# cs301_Team_15.net
KiCad netlist of a schematic drawn in Altium Designer
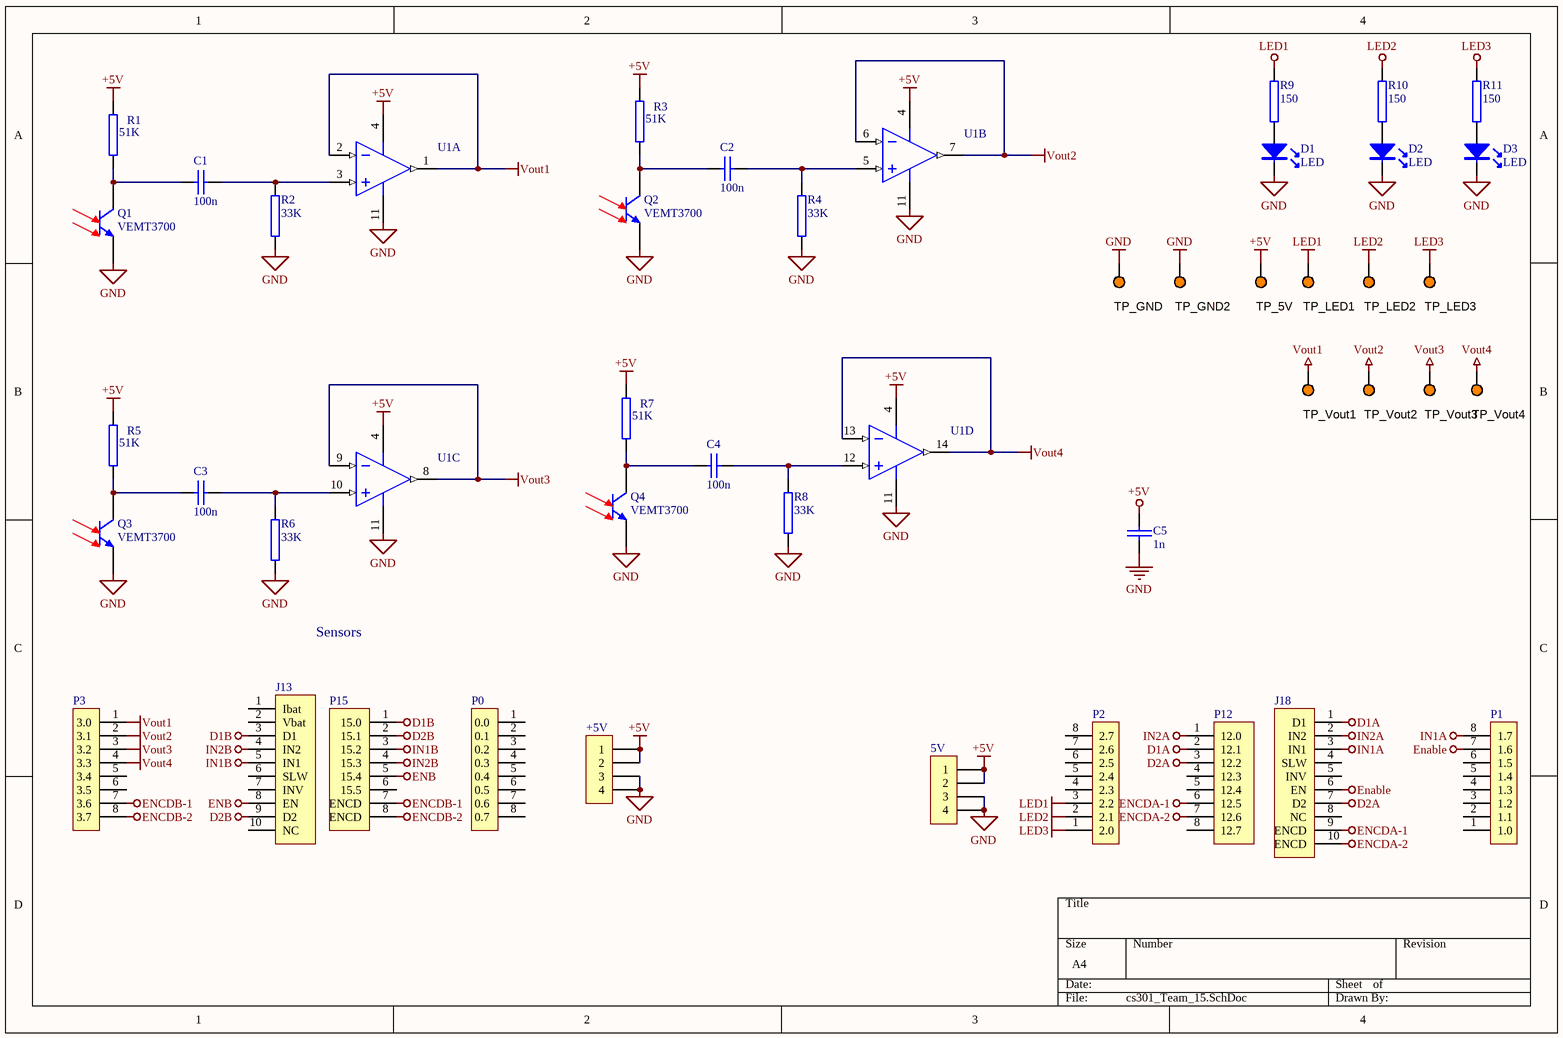
[diagram p0: cs301_Team_15.SchDoc]

(export (version "E")
  (design (tool "Eeschema 10.0.6"))
  (components
    (comp (ref "+5V")
      (value "5V")
      (footprint "IDC4")
      (description "Connector")
      (libsource (lib "Miscellaneous Devices") (part "CON4"))
    )
    (comp (ref "5V")
      (value "5V")
      (footprint "IDC4")
      (description "Connector")
      (libsource (lib "Miscellaneous Devices") (part "CON4"))
    )
    (comp (ref "C1")
      (value "100n")
      (footprint "CCAP-5P0")
      (description "TH ceramic capacitor with 5mm pitch")
      (libsource (lib "EE209_Library") (part "CerCap_TH_5P0"))
    )
    (comp (ref "C2")
      (value "100n")
      (footprint "CCAP-5P0")
      (description "TH ceramic capacitor with 5mm pitch")
      (libsource (lib "EE209_Library") (part "CerCap_TH_5P0"))
    )
    (comp (ref "C3")
      (value "100n")
      (footprint "CCAP-5P0")
      (description "TH ceramic capacitor with 5mm pitch")
      (libsource (lib "EE209_Library") (part "CerCap_TH_5P0"))
    )
    (comp (ref "C4")
      (value "100n")
      (footprint "CCAP-5P0")
      (description "TH ceramic capacitor with 5mm pitch")
      (libsource (lib "EE209_Library") (part "CerCap_TH_5P0"))
    )
    (comp (ref "C5")
      (value "1n")
      (footprint "CCAP-5P0")
      (description "TH ceramic capacitor with 5mm pitch")
      (libsource (lib "EE209_Library") (part "CerCap_TH_5P0"))
    )
    (comp (ref "D1") (value "LED") (footprint "LED0.1/5MM") (libsource (lib "COMSYS301_2013") (part "LED")))
    (comp (ref "D2") (value "LED") (footprint "LED0.1/5MM") (libsource (lib "COMSYS301_2013") (part "LED")))
    (comp (ref "D3") (value "LED") (footprint "LED0.1/5MM") (libsource (lib "COMSYS301_2013") (part "LED")))
    (comp (ref "J13")
      (value "CON10")
      (footprint "idc10")
      (description "Connector")
      (libsource (lib "Miscellaneous Devices") (part "CON10"))
    )
    (comp (ref "J18")
      (value "CON10")
      (footprint "IDC10")
      (description "Connector")
      (libsource (lib "") (part "CON10_1"))
    )
    (comp (ref "P0")
      (value "P0")
      (footprint "idc8")
      (description "Connector")
      (libsource (lib "") (part "CON8_1"))
    )
    (comp (ref "P1")
      (value "P1")
      (footprint "idc8")
      (description "Connector")
      (libsource (lib "") (part "CON8_2"))
    )
    (comp (ref "P2")
      (value "P2")
      (footprint "idc8")
      (description "Connector")
      (libsource (lib "") (part "CON8_2"))
    )
    (comp (ref "P3")
      (value "P3")
      (footprint "idc8")
      (description "Connector")
      (libsource (lib "Miscellaneous Devices") (part "CON8"))
    )
    (comp (ref "P12")
      (value "P12")
      (footprint "idc8")
      (description "Connector")
      (libsource (lib "") (part "CON8_1_1"))
    )
    (comp (ref "P15")
      (value "P15")
      (footprint "idc8")
      (description "Connector")
      (libsource (lib "Miscellaneous Devices") (part "CON8_1"))
    )
    (comp (ref "Q1")
      (value "VEMT3700")
      (footprint "VEMT3700")
      (description "Silicon NPN Phototransistor")
      (libsource (lib "COMSYS301_2013") (part "VEMT3700"))
    )
    (comp (ref "Q2")
      (value "VEMT3700")
      (footprint "VEMT3700")
      (description "Silicon NPN Phototransistor")
      (libsource (lib "COMSYS301_2013") (part "VEMT3700"))
    )
    (comp (ref "Q3")
      (value "VEMT3700")
      (footprint "VEMT3700")
      (description "Silicon NPN Phototransistor")
      (libsource (lib "COMSYS301_2013") (part "VEMT3700"))
    )
    (comp (ref "Q4")
      (value "VEMT3700")
      (footprint "VEMT3700")
      (description "Silicon NPN Phototransistor")
      (libsource (lib "COMSYS301_2013") (part "VEMT3700"))
    )
    (comp (ref "R1") (value "51K") (footprint "AXIAL0.4") (libsource (lib "COMSYS301_2013") (part "RES2")))
    (comp (ref "R2") (value "33K") (footprint "AXIAL0.4") (libsource (lib "COMSYS301_2013") (part "RES2")))
    (comp (ref "R3") (value "51K") (footprint "AXIAL0.4") (libsource (lib "COMSYS301_2013") (part "RES2")))
    (comp (ref "R4") (value "33K") (footprint "AXIAL0.4") (libsource (lib "COMSYS301_2013") (part "RES2")))
    (comp (ref "R5") (value "51K") (footprint "AXIAL0.4") (libsource (lib "COMSYS301_2013") (part "RES2")))
    (comp (ref "R6") (value "33K") (footprint "AXIAL0.4") (libsource (lib "COMSYS301_2013") (part "RES2")))
    (comp (ref "R7") (value "51K") (footprint "AXIAL0.4") (libsource (lib "COMSYS301_2013") (part "RES2")))
    (comp (ref "R8") (value "33K") (footprint "AXIAL0.4") (libsource (lib "COMSYS301_2013") (part "RES2")))
    (comp (ref "R9") (value "150") (footprint "AXIAL0.4") (libsource (lib "COMSYS301_2013") (part "RES2")))
    (comp (ref "R10") (value "150") (footprint "AXIAL0.4") (libsource (lib "COMSYS301_2013") (part "RES2")))
    (comp (ref "R11") (value "150") (footprint "AXIAL0.4") (libsource (lib "COMSYS301_2013") (part "RES2")))
    (comp (ref "TP_5V")
      (value "5003")
      (footprint "TP_TH")
      (description "Test Point, Orange, 1-Pin THD, RoHS")
      (libsource (lib "EE209_Library") (part "TestPoint"))
    )
    (comp (ref "TP_GND")
      (value "5003")
      (footprint "TP_TH")
      (description "Test Point, Orange, 1-Pin THD, RoHS")
      (libsource (lib "EE209_Library") (part "TestPoint"))
    )
    (comp (ref "TP_GND2")
      (value "5003")
      (footprint "TP_TH")
      (description "Test Point, Orange, 1-Pin THD, RoHS")
      (libsource (lib "EE209_Library") (part "TestPoint"))
    )
    (comp (ref "TP_LED1")
      (value "5003")
      (footprint "TP_TH")
      (description "Test Point, Orange, 1-Pin THD, RoHS")
      (libsource (lib "EE209_Library") (part "TestPoint"))
    )
    (comp (ref "TP_LED2")
      (value "5003")
      (footprint "TP_TH")
      (description "Test Point, Orange, 1-Pin THD, RoHS")
      (libsource (lib "EE209_Library") (part "TestPoint"))
    )
    (comp (ref "TP_LED3")
      (value "5003")
      (footprint "TP_TH")
      (description "Test Point, Orange, 1-Pin THD, RoHS")
      (libsource (lib "EE209_Library") (part "TestPoint"))
    )
    (comp (ref "TP_Vout1")
      (value "5003")
      (footprint "TP_TH")
      (description "Test Point, Orange, 1-Pin THD, RoHS")
      (libsource (lib "EE209_Library") (part "TestPoint"))
    )
    (comp (ref "TP_Vout2")
      (value "5003")
      (footprint "TP_TH")
      (description "Test Point, Orange, 1-Pin THD, RoHS")
      (libsource (lib "EE209_Library") (part "TestPoint"))
    )
    (comp (ref "TP_Vout3")
      (value "5003")
      (footprint "TP_TH")
      (description "Test Point, Orange, 1-Pin THD, RoHS")
      (libsource (lib "EE209_Library") (part "TestPoint"))
    )
    (comp (ref "TP_Vout4")
      (value "5003")
      (footprint "TP_TH")
      (description "Test Point, Orange, 1-Pin THD, RoHS")
      (libsource (lib "EE209_Library") (part "TestPoint"))
    )
    (comp (ref "U1")
      (value "LM324")
      (footprint "DIP-14")
      (description "IC OPAMP GP 14DIP")
      (fields
        (field (name "MANUFACTURER") "ON Semiconductor")
        (field (name "MANUFACTURER PART NUMBER") "LM324N")
      )
      (libsource (lib "EE209_Library") (part "LM324N_TH_DIP16"))
    )
  )
  (nets
    (net (code "1") (name "+5V") (class "Default")
      (node (ref "+5V") (pin "1") (pinfunction "1_1") (pintype "passive"))
      (node (ref "+5V") (pin "2") (pinfunction "2_2") (pintype "passive"))
      (node (ref "5V") (pin "1") (pinfunction "1_1") (pintype "passive"))
      (node (ref "5V") (pin "2") (pinfunction "2_2") (pintype "passive"))
      (node (ref "C5") (pin "1") (pinfunction "1_1") (pintype "passive"))
      (node (ref "R1") (pin "2") (pinfunction "2_2") (pintype "passive"))
      (node (ref "R3") (pin "2") (pinfunction "2_2") (pintype "passive"))
      (node (ref "R5") (pin "2") (pinfunction "2_2") (pintype "passive"))
      (node (ref "R7") (pin "2") (pinfunction "2_2") (pintype "passive"))
      (node (ref "TP_5V") (pin "1") (pinfunction "1_1") (pintype "passive"))
      (node (ref "U1") (pin "4") (pinfunction "VDD_4") (pintype "power_in"))
    )
    (net (code "2") (name "D1A") (class "Default")
      (node (ref "J18") (pin "1") (pinfunction "D1_1") (pintype "passive"))
      (node (ref "P12") (pin "2") (pinfunction "12.1_2") (pintype "passive"))
    )
    (net (code "3") (name "D1B") (class "Default")
      (node (ref "J13") (pin "3") (pinfunction "D1_3") (pintype "passive"))
      (node (ref "P15") (pin "1") (pinfunction "15.0_1") (pintype "passive"))
    )
    (net (code "4") (name "D2A") (class "Default")
      (node (ref "J18") (pin "7") (pinfunction "D2_7") (pintype "passive"))
      (node (ref "P12") (pin "3") (pinfunction "12.2_3") (pintype "passive"))
    )
    (net (code "5") (name "D2B") (class "Default")
      (node (ref "J13") (pin "9") (pinfunction "D2_9") (pintype "passive"))
      (node (ref "P15") (pin "2") (pinfunction "15.1_2") (pintype "passive"))
    )
    (net (code "6") (name "ENB") (class "Default")
      (node (ref "J13") (pin "8") (pinfunction "EN_8") (pintype "passive"))
      (node (ref "P15") (pin "5") (pinfunction "15.4_5") (pintype "passive"))
    )
    (net (code "7") (name "ENCDA-1") (class "Default")
      (node (ref "J18") (pin "9") (pinfunction "ENCD_9") (pintype "passive"))
      (node (ref "P12") (pin "6") (pinfunction "12.5_6") (pintype "passive"))
    )
    (net (code "8") (name "ENCDA-2") (class "Default")
      (node (ref "J18") (pin "10") (pinfunction "ENCD_10") (pintype "passive"))
      (node (ref "P12") (pin "7") (pinfunction "12.6_7") (pintype "passive"))
    )
    (net (code "9") (name "ENCDB-1") (class "Default")
      (node (ref "P15") (pin "7") (pinfunction "ENCD_7") (pintype "passive"))
      (node (ref "P3") (pin "7") (pinfunction "3.6_7") (pintype "passive"))
    )
    (net (code "10") (name "ENCDB-2") (class "Default")
      (node (ref "P15") (pin "8") (pinfunction "ENCD_8") (pintype "passive"))
      (node (ref "P3") (pin "8") (pinfunction "3.7_8") (pintype "passive"))
    )
    (net (code "11") (name "Enable") (class "Default")
      (node (ref "J18") (pin "6") (pinfunction "EN_6") (pintype "passive"))
      (node (ref "P1") (pin "7") (pinfunction "2.6_7") (pintype "passive"))
    )
    (net (code "12") (name "GND") (class "Default")
      (node (ref "+5V") (pin "3") (pinfunction "3_3") (pintype "passive"))
      (node (ref "+5V") (pin "4") (pinfunction "4_4") (pintype "passive"))
      (node (ref "5V") (pin "3") (pinfunction "3_3") (pintype "passive"))
      (node (ref "5V") (pin "4") (pinfunction "4_4") (pintype "passive"))
      (node (ref "C5") (pin "2") (pinfunction "2_2") (pintype "passive"))
      (node (ref "D1") (pin "K") (pinfunction "2_K") (pintype "passive"))
      (node (ref "D2") (pin "K") (pinfunction "2_K") (pintype "passive"))
      (node (ref "D3") (pin "K") (pinfunction "2_K") (pintype "passive"))
      (node (ref "Q1") (pin "2") (pinfunction "E_2") (pintype "passive"))
      (node (ref "Q2") (pin "2") (pinfunction "E_2") (pintype "passive"))
      (node (ref "Q3") (pin "2") (pinfunction "E_2") (pintype "passive"))
      (node (ref "Q4") (pin "2") (pinfunction "E_2") (pintype "passive"))
      (node (ref "R2") (pin "1") (pinfunction "1_1") (pintype "passive"))
      (node (ref "R4") (pin "1") (pinfunction "1_1") (pintype "passive"))
      (node (ref "R6") (pin "1") (pinfunction "1_1") (pintype "passive"))
      (node (ref "R8") (pin "1") (pinfunction "1_1") (pintype "passive"))
      (node (ref "TP_GND") (pin "1") (pinfunction "1_1") (pintype "passive"))
      (node (ref "TP_GND2") (pin "1") (pinfunction "1_1") (pintype "passive"))
      (node (ref "U1") (pin "11") (pinfunction "VSS_11") (pintype "power_in"))
    )
    (net (code "13") (name "IN1A") (class "Default")
      (node (ref "J18") (pin "3") (pinfunction "IN1_3") (pintype "passive"))
      (node (ref "P1") (pin "8") (pinfunction "2.7_8") (pintype "passive"))
    )
    (net (code "14") (name "IN1B") (class "Default")
      (node (ref "J13") (pin "5") (pinfunction "IN1_5") (pintype "passive"))
      (node (ref "P15") (pin "3") (pinfunction "15.2_3") (pintype "passive"))
    )
    (net (code "15") (name "IN2A") (class "Default")
      (node (ref "J18") (pin "2") (pinfunction "IN2_2") (pintype "passive"))
      (node (ref "P12") (pin "1") (pinfunction "12.0_1") (pintype "passive"))
    )
    (net (code "16") (name "IN2B") (class "Default")
      (node (ref "J13") (pin "4") (pinfunction "IN2_4") (pintype "passive"))
      (node (ref "P15") (pin "4") (pinfunction "15.3_4") (pintype "passive"))
    )
    (net (code "17") (name "LED1") (class "Default")
      (node (ref "P2") (pin "3") (pinfunction "2.2_3") (pintype "passive"))
      (node (ref "R9") (pin "2") (pinfunction "2_2") (pintype "passive"))
      (node (ref "TP_LED1") (pin "1") (pinfunction "1_1") (pintype "passive"))
    )
    (net (code "18") (name "LED2") (class "Default")
      (node (ref "P2") (pin "2") (pinfunction "2.1_2") (pintype "passive"))
      (node (ref "R10") (pin "2") (pinfunction "2_2") (pintype "passive"))
      (node (ref "TP_LED2") (pin "1") (pinfunction "1_1") (pintype "passive"))
    )
    (net (code "19") (name "LED3") (class "Default")
      (node (ref "P2") (pin "1") (pinfunction "2.0_1") (pintype "passive"))
      (node (ref "R11") (pin "1") (pinfunction "1_1") (pintype "passive"))
      (node (ref "TP_LED3") (pin "1") (pinfunction "1_1") (pintype "passive"))
    )
    (net (code "20") (name "Net-(D1-1)") (class "Default")
      (node (ref "D1") (pin "A") (pinfunction "1_A") (pintype "passive"))
      (node (ref "R9") (pin "1") (pinfunction "1_1") (pintype "passive"))
    )
    (net (code "21") (name "Net-(D2-1)") (class "Default")
      (node (ref "D2") (pin "A") (pinfunction "1_A") (pintype "passive"))
      (node (ref "R10") (pin "1") (pinfunction "1_1") (pintype "passive"))
    )
    (net (code "22") (name "Net-(D3-1)") (class "Default")
      (node (ref "D3") (pin "A") (pinfunction "1_A") (pintype "passive"))
      (node (ref "R11") (pin "2") (pinfunction "2_2") (pintype "passive"))
    )
    (net (code "23") (name "Net-(Q1-C)") (class "Default")
      (node (ref "C1") (pin "1") (pinfunction "1_1") (pintype "passive"))
      (node (ref "Q1") (pin "1") (pinfunction "C_1") (pintype "passive"))
      (node (ref "R1") (pin "1") (pinfunction "1_1") (pintype "passive"))
    )
    (net (code "24") (name "Net-(Q2-C)") (class "Default")
      (node (ref "C2") (pin "1") (pinfunction "1_1") (pintype "passive"))
      (node (ref "Q2") (pin "1") (pinfunction "C_1") (pintype "passive"))
      (node (ref "R3") (pin "1") (pinfunction "1_1") (pintype "passive"))
    )
    (net (code "25") (name "Net-(Q3-C)") (class "Default")
      (node (ref "C3") (pin "1") (pinfunction "1_1") (pintype "passive"))
      (node (ref "Q3") (pin "1") (pinfunction "C_1") (pintype "passive"))
      (node (ref "R5") (pin "1") (pinfunction "1_1") (pintype "passive"))
    )
    (net (code "26") (name "Net-(Q4-C)") (class "Default")
      (node (ref "C4") (pin "1") (pinfunction "1_1") (pintype "passive"))
      (node (ref "Q4") (pin "1") (pinfunction "C_1") (pintype "passive"))
      (node (ref "R7") (pin "1") (pinfunction "1_1") (pintype "passive"))
    )
    (net (code "27") (name "Net-(U1A-VINA+)") (class "Default")
      (node (ref "C1") (pin "2") (pinfunction "2_2") (pintype "passive"))
      (node (ref "R2") (pin "2") (pinfunction "2_2") (pintype "passive"))
      (node (ref "U1") (pin "3") (pinfunction "VINA+_3") (pintype "input"))
    )
    (net (code "28") (name "Net-(U1B-VINB+)") (class "Default")
      (node (ref "C2") (pin "2") (pinfunction "2_2") (pintype "passive"))
      (node (ref "R4") (pin "2") (pinfunction "2_2") (pintype "passive"))
      (node (ref "U1") (pin "5") (pinfunction "VINB+_5") (pintype "input"))
    )
    (net (code "29") (name "Net-(U1C-VINC+)") (class "Default")
      (node (ref "C3") (pin "2") (pinfunction "2_2") (pintype "passive"))
      (node (ref "R6") (pin "2") (pinfunction "2_2") (pintype "passive"))
      (node (ref "U1") (pin "10") (pinfunction "VINC+_10") (pintype "input"))
    )
    (net (code "30") (name "Net-(U1D-VIND+)") (class "Default")
      (node (ref "C4") (pin "2") (pinfunction "2_2") (pintype "passive"))
      (node (ref "R8") (pin "2") (pinfunction "2_2") (pintype "passive"))
      (node (ref "U1") (pin "12") (pinfunction "VIND+_12") (pintype "input"))
    )
    (net (code "31") (name "Vout1") (class "Default")
      (node (ref "P3") (pin "1") (pinfunction "3.0_1") (pintype "passive"))
      (node (ref "TP_Vout1") (pin "1") (pinfunction "1_1") (pintype "passive"))
      (node (ref "U1") (pin "1") (pinfunction "VOUTA_1") (pintype "output"))
      (node (ref "U1") (pin "2") (pinfunction "VINA-_2") (pintype "input"))
    )
    (net (code "32") (name "Vout2") (class "Default")
      (node (ref "P3") (pin "2") (pinfunction "3.1_2") (pintype "passive"))
      (node (ref "TP_Vout2") (pin "1") (pinfunction "1_1") (pintype "passive"))
      (node (ref "U1") (pin "6") (pinfunction "VINB-_6") (pintype "input"))
      (node (ref "U1") (pin "7") (pinfunction "VOUTB_7") (pintype "output"))
    )
    (net (code "33") (name "Vout3") (class "Default")
      (node (ref "P3") (pin "3") (pinfunction "3.2_3") (pintype "passive"))
      (node (ref "TP_Vout3") (pin "1") (pinfunction "1_1") (pintype "passive"))
      (node (ref "U1") (pin "8") (pinfunction "VOUTC_8") (pintype "output"))
      (node (ref "U1") (pin "9") (pinfunction "VINC-_9") (pintype "input"))
    )
    (net (code "34") (name "Vout4") (class "Default")
      (node (ref "P3") (pin "4") (pinfunction "3.3_4") (pintype "passive"))
      (node (ref "TP_Vout4") (pin "1") (pinfunction "1_1") (pintype "passive"))
      (node (ref "U1") (pin "13") (pinfunction "VIND-_13") (pintype "input"))
      (node (ref "U1") (pin "14") (pinfunction "VOUTD_14") (pintype "output"))
    )
    (net (code "35") (name "unconnected-(J13-INV-Pad7)") (class "Default")
      (node (ref "J13") (pin "7") (pinfunction "INV_7") (pintype "passive"))
    )
    (net (code "36") (name "unconnected-(J13-Ibat-Pad1)") (class "Default")
      (node (ref "J13") (pin "1") (pinfunction "Ibat_1") (pintype "passive"))
    )
    (net (code "37") (name "unconnected-(J13-NC-Pad10)") (class "Default")
      (node (ref "J13") (pin "10") (pinfunction "NC_10") (pintype "passive"))
    )
    (net (code "38") (name "unconnected-(J13-SLW-Pad6)") (class "Default")
      (node (ref "J13") (pin "6") (pinfunction "SLW_6") (pintype "passive"))
    )
    (net (code "39") (name "unconnected-(J13-Vbat-Pad2)") (class "Default")
      (node (ref "J13") (pin "2") (pinfunction "Vbat_2") (pintype "passive"))
    )
    (net (code "40") (name "unconnected-(J18-INV-Pad5)") (class "Default")
      (node (ref "J18") (pin "5") (pinfunction "INV_5") (pintype "passive"))
    )
    (net (code "41") (name "unconnected-(J18-NC-Pad8)") (class "Default")
      (node (ref "J18") (pin "8") (pinfunction "NC_8") (pintype "passive"))
    )
    (net (code "42") (name "unconnected-(J18-SLW-Pad4)") (class "Default")
      (node (ref "J18") (pin "4") (pinfunction "SLW_4") (pintype "passive"))
    )
    (net (code "43") (name "unconnected-(P0-0.0-Pad1)") (class "Default")
      (node (ref "P0") (pin "1") (pinfunction "0.0_1") (pintype "passive"))
    )
    (net (code "44") (name "unconnected-(P0-0.1-Pad2)") (class "Default")
      (node (ref "P0") (pin "2") (pinfunction "0.1_2") (pintype "passive"))
    )
    (net (code "45") (name "unconnected-(P0-0.2-Pad3)") (class "Default")
      (node (ref "P0") (pin "3") (pinfunction "0.2_3") (pintype "passive"))
    )
    (net (code "46") (name "unconnected-(P0-0.3-Pad4)") (class "Default")
      (node (ref "P0") (pin "4") (pinfunction "0.3_4") (pintype "passive"))
    )
    (net (code "47") (name "unconnected-(P0-0.4-Pad5)") (class "Default")
      (node (ref "P0") (pin "5") (pinfunction "0.4_5") (pintype "passive"))
    )
    (net (code "48") (name "unconnected-(P0-0.5-Pad6)") (class "Default")
      (node (ref "P0") (pin "6") (pinfunction "0.5_6") (pintype "passive"))
    )
    (net (code "49") (name "unconnected-(P0-0.6-Pad7)") (class "Default")
      (node (ref "P0") (pin "7") (pinfunction "0.6_7") (pintype "passive"))
    )
    (net (code "50") (name "unconnected-(P0-0.7-Pad8)") (class "Default")
      (node (ref "P0") (pin "8") (pinfunction "0.7_8") (pintype "passive"))
    )
    (net (code "51") (name "unconnected-(P1-2.0-Pad1)") (class "Default")
      (node (ref "P1") (pin "1") (pinfunction "2.0_1") (pintype "passive"))
    )
    (net (code "52") (name "unconnected-(P1-2.1-Pad2)") (class "Default")
      (node (ref "P1") (pin "2") (pinfunction "2.1_2") (pintype "passive"))
    )
    (net (code "53") (name "unconnected-(P1-2.2-Pad3)") (class "Default")
      (node (ref "P1") (pin "3") (pinfunction "2.2_3") (pintype "passive"))
    )
    (net (code "54") (name "unconnected-(P1-2.3-Pad4)") (class "Default")
      (node (ref "P1") (pin "4") (pinfunction "2.3_4") (pintype "passive"))
    )
    (net (code "55") (name "unconnected-(P1-2.4-Pad5)") (class "Default")
      (node (ref "P1") (pin "5") (pinfunction "2.4_5") (pintype "passive"))
    )
    (net (code "56") (name "unconnected-(P1-2.5-Pad6)") (class "Default")
      (node (ref "P1") (pin "6") (pinfunction "2.5_6") (pintype "passive"))
    )
    (net (code "57") (name "unconnected-(P2-2.3-Pad4)") (class "Default")
      (node (ref "P2") (pin "4") (pinfunction "2.3_4") (pintype "passive"))
    )
    (net (code "58") (name "unconnected-(P2-2.4-Pad5)") (class "Default")
      (node (ref "P2") (pin "5") (pinfunction "2.4_5") (pintype "passive"))
    )
    (net (code "59") (name "unconnected-(P2-2.5-Pad6)") (class "Default")
      (node (ref "P2") (pin "6") (pinfunction "2.5_6") (pintype "passive"))
    )
    (net (code "60") (name "unconnected-(P2-2.6-Pad7)") (class "Default")
      (node (ref "P2") (pin "7") (pinfunction "2.6_7") (pintype "passive"))
    )
    (net (code "61") (name "unconnected-(P2-2.7-Pad8)") (class "Default")
      (node (ref "P2") (pin "8") (pinfunction "2.7_8") (pintype "passive"))
    )
    (net (code "62") (name "unconnected-(P3-3.4-Pad5)") (class "Default")
      (node (ref "P3") (pin "5") (pinfunction "3.4_5") (pintype "passive"))
    )
    (net (code "63") (name "unconnected-(P3-3.5-Pad6)") (class "Default")
      (node (ref "P3") (pin "6") (pinfunction "3.5_6") (pintype "passive"))
    )
    (net (code "64") (name "unconnected-(P12-12.3-Pad4)") (class "Default")
      (node (ref "P12") (pin "4") (pinfunction "12.3_4") (pintype "passive"))
    )
    (net (code "65") (name "unconnected-(P12-12.4-Pad5)") (class "Default")
      (node (ref "P12") (pin "5") (pinfunction "12.4_5") (pintype "passive"))
    )
    (net (code "66") (name "unconnected-(P12-12.7-Pad8)") (class "Default")
      (node (ref "P12") (pin "8") (pinfunction "12.7_8") (pintype "passive"))
    )
    (net (code "67") (name "unconnected-(P15-15.5-Pad6)") (class "Default")
      (node (ref "P15") (pin "6") (pinfunction "15.5_6") (pintype "passive"))
    )
  )
)
